# Dustbike_Core_Top.net
KiCad netlist of a schematic drawn in Altium Designer
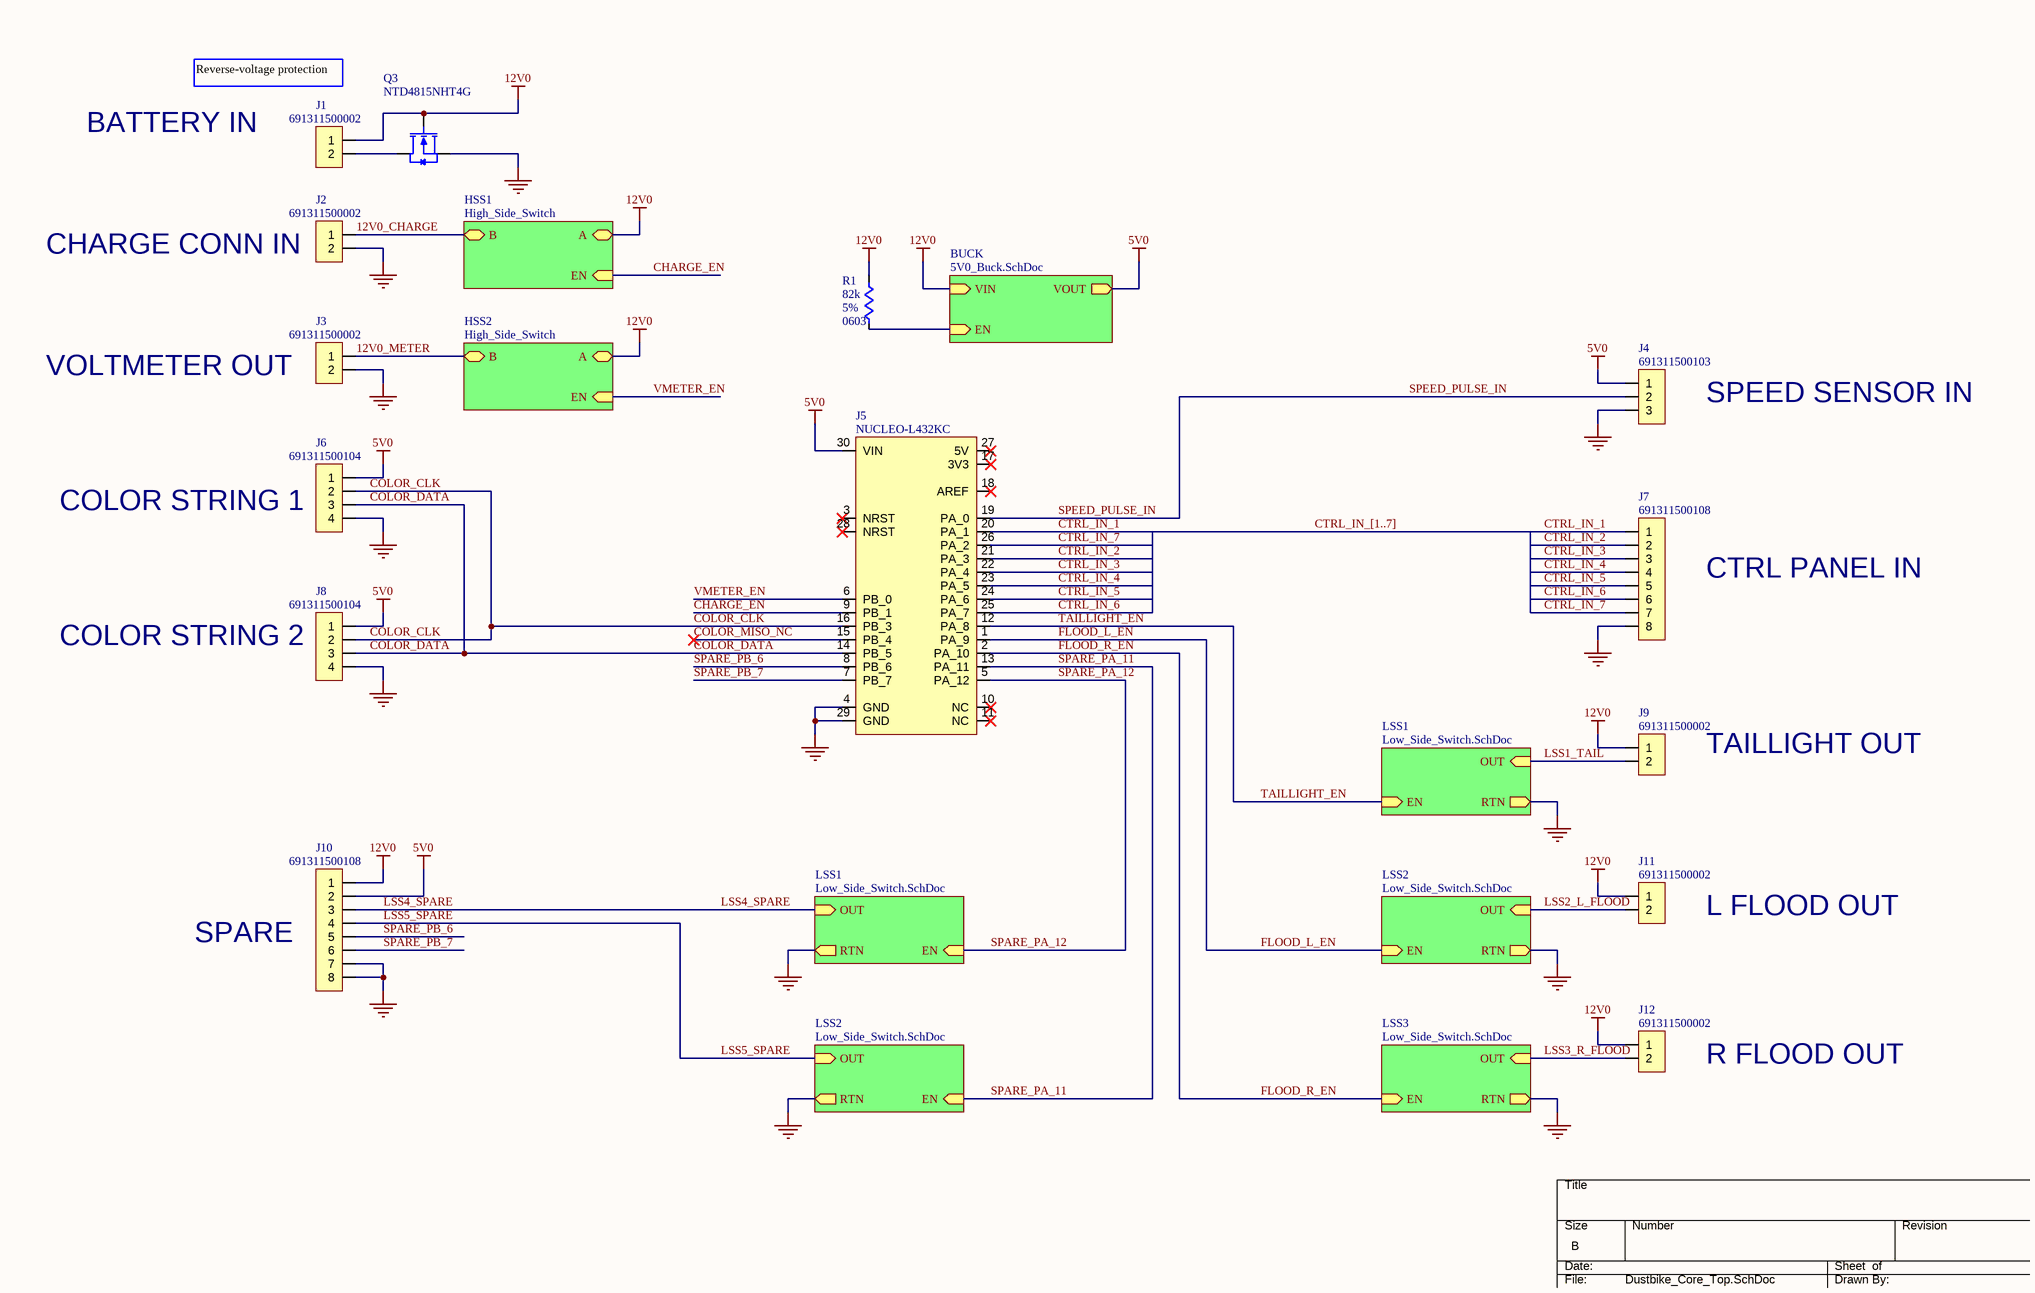
[diagram p0: Dustbike_Core_Top.SchDoc]

(export (version "E")
  (design (tool "Eeschema 10.0.6"))
  (components
    (comp (ref "J1")
      (value "HDR_2POS")
      (footprint "WURTH_691311500002")
      (description "TERM BLOCK HDR 2POS VERT 5.08MM")
      (fields (field (name "MANUFACTURER PART NUMBER 1") "691311500002"))
      (libsource (lib "") (part "HDR_2POS_1"))
    )
    (comp (ref "J2")
      (value "HDR_2POS")
      (footprint "WURTH_691311500002")
      (description "TERM BLOCK HDR 2POS VERT 5.08MM")
      (fields (field (name "MANUFACTURER PART NUMBER 1") "691311500002"))
      (libsource (lib "") (part "HDR_2POS_1"))
    )
    (comp (ref "J3")
      (value "HDR_2POS")
      (footprint "WURTH_691311500002")
      (description "TERM BLOCK HDR 2POS VERT 5.08MM")
      (fields (field (name "MANUFACTURER PART NUMBER 1") "691311500002"))
      (libsource (lib "") (part "HDR_2POS_1"))
    )
    (comp (ref "J4")
      (value "HDR_3POS")
      (footprint "WURTH_691311500103")
      (description "TERM BLOCK HDR 3POS VERT 5.08MM")
      (fields (field (name "MANUFACTURER PART NUMBER 1") "691311500103"))
      (libsource (lib "connectors") (part "HDR_3POS"))
    )
    (comp (ref "J5")
      (value "NUCLEO_NANO")
      (footprint "NANO_HEADER")
      (description "NUCLEO-32 STM32L432KC EVAL BRD")
      (fields (field (name "MANUFACTURER PART NUMBER 1") "NUCLEO-L432KC"))
      (libsource (lib "ics") (part "NUCLEO_NANO"))
    )
    (comp (ref "J6")
      (value "HDR_4POS")
      (footprint "WURTH_691311500104")
      (description "TERM BLOCK HDR 4POS VERT 5.08MM")
      (fields (field (name "MANUFACTURER PART NUMBER 1") "691311500104"))
      (libsource (lib "connectors") (part "HDR_4POS"))
    )
    (comp (ref "J7")
      (value "HDR_8POS")
      (footprint "WURTH_691311500108")
      (description "TERM BLOCK HDR 8POS VERT 5.08MM")
      (fields (field (name "MANUFACTURER PART NUMBER 1") "691311500108"))
      (libsource (lib "connectors") (part "HDR_8POS"))
    )
    (comp (ref "J8")
      (value "HDR_4POS")
      (footprint "WURTH_691311500104")
      (description "TERM BLOCK HDR 4POS VERT 5.08MM")
      (fields (field (name "MANUFACTURER PART NUMBER 1") "691311500104"))
      (libsource (lib "connectors") (part "HDR_4POS"))
    )
    (comp (ref "J9")
      (value "HDR_2POS")
      (footprint "WURTH_691311500002")
      (description "TERM BLOCK HDR 2POS VERT 5.08MM")
      (fields (field (name "MANUFACTURER PART NUMBER 1") "691311500002"))
      (libsource (lib "connectors") (part "HDR_2POS"))
    )
    (comp (ref "J10")
      (value "HDR_8POS")
      (footprint "WURTH_691311500108")
      (description "TERM BLOCK HDR 8POS VERT 5.08MM")
      (fields (field (name "MANUFACTURER PART NUMBER 1") "691311500108"))
      (libsource (lib "") (part "HDR_8POS_1"))
    )
    (comp (ref "J11")
      (value "HDR_2POS")
      (footprint "WURTH_691311500002")
      (description "TERM BLOCK HDR 2POS VERT 5.08MM")
      (fields (field (name "MANUFACTURER PART NUMBER 1") "691311500002"))
      (libsource (lib "connectors") (part "HDR_2POS"))
    )
    (comp (ref "J12")
      (value "HDR_2POS")
      (footprint "WURTH_691311500002")
      (description "TERM BLOCK HDR 2POS VERT 5.08MM")
      (fields (field (name "MANUFACTURER PART NUMBER 1") "691311500002"))
      (libsource (lib "connectors") (part "HDR_2POS"))
    )
    (comp (ref "Q3")
      (value "NFET_SOT323")
      (footprint "DPAK228P991X238-3N_NTD4815NHT4G")
      (description "MOSFET N-CH 30V 6.9A/35A DPAK")
      (fields (field (name "MANUFACTURER PART NUMBER 1") "NTD4815NHT4G"))
      (libsource (lib "discretes") (part "NFET_SOT323"))
    )
    (comp (ref "R1")
      (value "82k")
      (footprint "RESC1508X09N")
      (description "RES 82K OHM 5% 0603")
      (fields (field (name "TOLERANCE") "5%") (field (name "PACKAGE") "0603") (field (name "Comment") "RES"))
      (libsource (lib "resistors") (part "RES"))
    )
  )
  (nets
    (net (code "1") (name "/12V0_CHARGE") (class "Default")
      (node (ref "J2") (pin "1") (pinfunction "1_1") (pintype "passive"))
    )
    (net (code "2") (name "/12V0_METER") (class "Default")
      (node (ref "J3") (pin "1") (pinfunction "1_1") (pintype "passive"))
    )
    (net (code "3") (name "/CHARGE_EN") (class "Default")
      (node (ref "J5") (pin "9") (pinfunction "PB_1_9") (pintype "passive"))
    )
    (net (code "4") (name "/COLOR_CLK") (class "Default")
      (node (ref "J5") (pin "16") (pinfunction "PB_3_16") (pintype "passive"))
      (node (ref "J6") (pin "2") (pinfunction "2_2") (pintype "passive"))
      (node (ref "J8") (pin "2") (pinfunction "2_2") (pintype "passive"))
    )
    (net (code "5") (name "/COLOR_DATA") (class "Default")
      (node (ref "J5") (pin "14") (pinfunction "PB_5_14") (pintype "passive"))
      (node (ref "J6") (pin "3") (pinfunction "3_3") (pintype "passive"))
      (node (ref "J8") (pin "3") (pinfunction "3_3") (pintype "passive"))
    )
    (net (code "6") (name "/COLOR_MISO_NC") (class "Default")
      (node (ref "J5") (pin "15") (pinfunction "PB_4_15") (pintype "passive+no_connect"))
    )
    (net (code "7") (name "/CTRL_IN_1") (class "Default")
      (node (ref "J5") (pin "20") (pinfunction "PA_1_20") (pintype "passive"))
      (node (ref "J7") (pin "1") (pinfunction "1_1") (pintype "passive"))
    )
    (net (code "8") (name "/CTRL_IN_2") (class "Default")
      (node (ref "J5") (pin "21") (pinfunction "PA_3_21") (pintype "passive"))
      (node (ref "J7") (pin "2") (pinfunction "2_2") (pintype "passive"))
    )
    (net (code "9") (name "/CTRL_IN_3") (class "Default")
      (node (ref "J5") (pin "22") (pinfunction "PA_4_22") (pintype "passive"))
      (node (ref "J7") (pin "3") (pinfunction "3_3") (pintype "passive"))
    )
    (net (code "10") (name "/CTRL_IN_4") (class "Default")
      (node (ref "J5") (pin "23") (pinfunction "PA_5_23") (pintype "passive"))
      (node (ref "J7") (pin "4") (pinfunction "4_4") (pintype "passive"))
    )
    (net (code "11") (name "/CTRL_IN_5") (class "Default")
      (node (ref "J5") (pin "24") (pinfunction "PA_6_24") (pintype "passive"))
      (node (ref "J7") (pin "5") (pinfunction "5_5") (pintype "passive"))
    )
    (net (code "12") (name "/CTRL_IN_6") (class "Default")
      (node (ref "J5") (pin "25") (pinfunction "PA_7_25") (pintype "passive"))
      (node (ref "J7") (pin "6") (pinfunction "6_6") (pintype "passive"))
    )
    (net (code "13") (name "/CTRL_IN_7") (class "Default")
      (node (ref "J5") (pin "26") (pinfunction "PA_2_26") (pintype "passive"))
      (node (ref "J7") (pin "7") (pinfunction "7_7") (pintype "passive"))
    )
    (net (code "15") (name "/EN") (class "Default")
      (node (ref "R1") (pin "1") (pinfunction "1_1") (pintype "passive"))
    )
    (net (code "16") (name "/FLOOD_L_EN") (class "Default")
      (node (ref "J5") (pin "1") (pinfunction "PA_9_1") (pintype "passive"))
    )
    (net (code "17") (name "/FLOOD_R_EN") (class "Default")
      (node (ref "J5") (pin "2") (pinfunction "PA_10_2") (pintype "passive"))
    )
    (net (code "18") (name "/LSS1_TAIL") (class "Default")
      (node (ref "J9") (pin "2") (pinfunction "2_2") (pintype "passive"))
    )
    (net (code "19") (name "/LSS2_L_FLOOD") (class "Default")
      (node (ref "J11") (pin "2") (pinfunction "2_2") (pintype "passive"))
    )
    (net (code "20") (name "/LSS3_R_FLOOD") (class "Default")
      (node (ref "J12") (pin "2") (pinfunction "2_2") (pintype "passive"))
    )
    (net (code "21") (name "/LSS4_SPARE") (class "Default")
      (node (ref "J10") (pin "3") (pinfunction "3_3") (pintype "passive"))
    )
    (net (code "22") (name "/LSS5_SPARE") (class "Default")
      (node (ref "J10") (pin "4") (pinfunction "4_4") (pintype "passive"))
    )
    (net (code "23") (name "/SPARE_PA_11") (class "Default")
      (node (ref "J5") (pin "13") (pinfunction "PA_11_13") (pintype "passive"))
    )
    (net (code "24") (name "/SPARE_PA_12") (class "Default")
      (node (ref "J5") (pin "5") (pinfunction "PA_12_5") (pintype "passive"))
    )
    (net (code "25") (name "/SPARE_PB_6") (class "Default")
      (node (ref "J10") (pin "5") (pinfunction "5_5") (pintype "passive"))
      (node (ref "J5") (pin "8") (pinfunction "PB_6_8") (pintype "passive"))
    )
    (net (code "26") (name "/SPARE_PB_7") (class "Default")
      (node (ref "J10") (pin "6") (pinfunction "6_6") (pintype "passive"))
      (node (ref "J5") (pin "7") (pinfunction "PB_7_7") (pintype "passive"))
    )
    (net (code "27") (name "/SPEED_PULSE_IN") (class "Default")
      (node (ref "J4") (pin "2") (pinfunction "2_2") (pintype "passive"))
      (node (ref "J5") (pin "19") (pinfunction "PA_0_19") (pintype "passive"))
    )
    (net (code "28") (name "/TAILLIGHT_EN") (class "Default")
      (node (ref "J5") (pin "12") (pinfunction "PA_8_12") (pintype "passive"))
    )
    (net (code "29") (name "/VMETER_EN") (class "Default")
      (node (ref "J5") (pin "6") (pinfunction "PB_0_6") (pintype "passive"))
    )
    (net (code "30") (name "5V0") (class "Default")
      (node (ref "J10") (pin "2") (pinfunction "2_2") (pintype "passive"))
      (node (ref "J4") (pin "1") (pinfunction "1_1") (pintype "passive"))
      (node (ref "J5") (pin "30") (pinfunction "VIN_30") (pintype "passive"))
      (node (ref "J6") (pin "1") (pinfunction "1_1") (pintype "passive"))
      (node (ref "J8") (pin "1") (pinfunction "1_1") (pintype "passive"))
    )
    (net (code "31") (name "12V0") (class "Default")
      (node (ref "J1") (pin "1") (pinfunction "1_1") (pintype "passive"))
      (node (ref "J10") (pin "1") (pinfunction "1_1") (pintype "passive"))
      (node (ref "J11") (pin "1") (pinfunction "1_1") (pintype "passive"))
      (node (ref "J12") (pin "1") (pinfunction "1_1") (pintype "passive"))
      (node (ref "J9") (pin "1") (pinfunction "1_1") (pintype "passive"))
      (node (ref "Q3") (pin "G") (pinfunction "G_G") (pintype "passive"))
      (node (ref "R1") (pin "2") (pinfunction "2_2") (pintype "passive"))
    )
    (net (code "32") (name "GND") (class "Default")
      (node (ref "J10") (pin "7") (pinfunction "7_7") (pintype "passive"))
      (node (ref "J10") (pin "8") (pinfunction "8_8") (pintype "passive"))
      (node (ref "J2") (pin "2") (pinfunction "2_2") (pintype "passive"))
      (node (ref "J3") (pin "2") (pinfunction "2_2") (pintype "passive"))
      (node (ref "J4") (pin "3") (pinfunction "3_3") (pintype "passive"))
      (node (ref "J5") (pin "29") (pinfunction "GND_29") (pintype "passive"))
      (node (ref "J5") (pin "4") (pinfunction "GND_4") (pintype "passive"))
      (node (ref "J6") (pin "4") (pinfunction "4_4") (pintype "passive"))
      (node (ref "J7") (pin "8") (pinfunction "8_8") (pintype "passive"))
      (node (ref "J8") (pin "4") (pinfunction "4_4") (pintype "passive"))
      (node (ref "Q3") (pin "S") (pinfunction "S_S") (pintype "passive"))
    )
    (net (code "33") (name "Net-(J1-Pad2)") (class "Default")
      (node (ref "J1") (pin "2") (pinfunction "2_2") (pintype "passive"))
      (node (ref "Q3") (pin "D") (pinfunction "D_D") (pintype "passive"))
    )
    (net (code "34") (name "unconnected-(J5-3V3-Pad17)") (class "Default")
      (node (ref "J5") (pin "17") (pinfunction "3V3_17") (pintype "passive+no_connect"))
    )
    (net (code "35") (name "unconnected-(J5-5V-Pad27)") (class "Default")
      (node (ref "J5") (pin "27") (pinfunction "5V_27") (pintype "passive+no_connect"))
    )
    (net (code "36") (name "unconnected-(J5-AREF-Pad18)") (class "Default")
      (node (ref "J5") (pin "18") (pinfunction "AREF_18") (pintype "passive+no_connect"))
    )
    (net (code "37") (name "unconnected-(J5-NC-Pad10)") (class "Default")
      (node (ref "J5") (pin "10") (pinfunction "NC_10") (pintype "passive+no_connect"))
    )
    (net (code "38") (name "unconnected-(J5-NC-Pad11)") (class "Default")
      (node (ref "J5") (pin "11") (pinfunction "NC_11") (pintype "passive+no_connect"))
    )
    (net (code "39") (name "unconnected-(J5-NRST-Pad3)") (class "Default")
      (node (ref "J5") (pin "3") (pinfunction "NRST_3") (pintype "passive+no_connect"))
    )
    (net (code "40") (name "unconnected-(J5-NRST-Pad28)") (class "Default")
      (node (ref "J5") (pin "28") (pinfunction "NRST_28") (pintype "passive+no_connect"))
    )
  )
)
